# Mechanical.net
KiCad netlist of a schematic drawn in Altium Designer
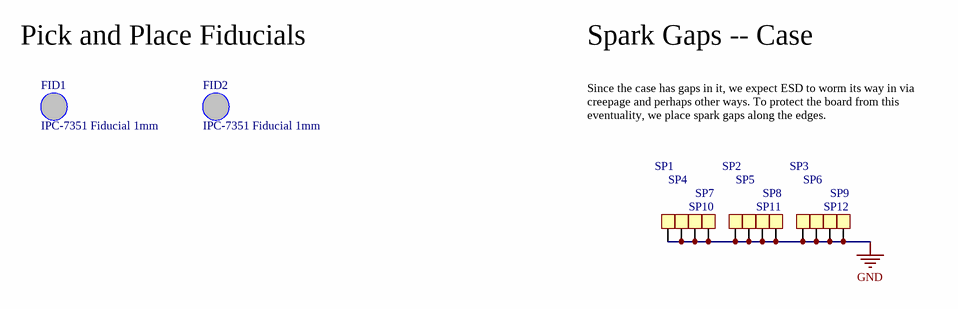
[diagram p0: Mechanical.SchDoc]

(export (version "E")
  (design (tool "Eeschema 10.0.6"))
  (components
    (comp (ref "FID1")
      (value "IPC-7351 Fiducial 1mm")
      (footprint "FIDUCIAL_1.5")
      (libsource (lib "Mechanical") (part "FIDUCIAL_1.5"))
    )
    (comp (ref "FID2")
      (value "IPC-7351 Fiducial 1mm")
      (footprint "FIDUCIAL_1.5")
      (libsource (lib "Mechanical") (part "FIDUCIAL_1.5"))
    )
    (comp (ref "SP1")
      (value "Spark Gap")
      (footprint "SparkGap")
      (description "Open square pad for spark gapping")
      (libsource (lib "PCBFeatures") (part "Spark Gap"))
    )
    (comp (ref "SP2")
      (value "Spark Gap")
      (footprint "SparkGap")
      (description "Open square pad for spark gapping")
      (libsource (lib "PCBFeatures") (part "Spark Gap"))
    )
    (comp (ref "SP3")
      (value "Spark Gap")
      (footprint "SparkGap")
      (description "Open square pad for spark gapping")
      (libsource (lib "PCBFeatures") (part "Spark Gap"))
    )
    (comp (ref "SP4")
      (value "Spark Gap")
      (footprint "SparkGap")
      (description "Open square pad for spark gapping")
      (libsource (lib "PCBFeatures") (part "Spark Gap"))
    )
    (comp (ref "SP5")
      (value "Spark Gap")
      (footprint "SparkGap")
      (description "Open square pad for spark gapping")
      (libsource (lib "PCBFeatures") (part "Spark Gap"))
    )
    (comp (ref "SP6")
      (value "Spark Gap")
      (footprint "SparkGap")
      (description "Open square pad for spark gapping")
      (libsource (lib "PCBFeatures") (part "Spark Gap"))
    )
    (comp (ref "SP7")
      (value "Spark Gap")
      (footprint "SparkGap")
      (description "Open square pad for spark gapping")
      (libsource (lib "PCBFeatures") (part "Spark Gap"))
    )
    (comp (ref "SP8")
      (value "Spark Gap")
      (footprint "SparkGap")
      (description "Open square pad for spark gapping")
      (libsource (lib "PCBFeatures") (part "Spark Gap"))
    )
    (comp (ref "SP9")
      (value "Spark Gap")
      (footprint "SparkGap")
      (description "Open square pad for spark gapping")
      (libsource (lib "PCBFeatures") (part "Spark Gap"))
    )
    (comp (ref "SP10")
      (value "Spark Gap")
      (footprint "SparkGap")
      (description "Open square pad for spark gapping")
      (libsource (lib "PCBFeatures") (part "Spark Gap"))
    )
    (comp (ref "SP11")
      (value "Spark Gap")
      (footprint "SparkGap")
      (description "Open square pad for spark gapping")
      (libsource (lib "PCBFeatures") (part "Spark Gap"))
    )
    (comp (ref "SP12")
      (value "Spark Gap")
      (footprint "SparkGap")
      (description "Open square pad for spark gapping")
      (libsource (lib "PCBFeatures") (part "Spark Gap"))
    )
  )
  (nets
    (net (code "1") (name "GND") (class "Default")
      (node (ref "SP1") (pin "1") (pinfunction "1_1") (pintype "passive"))
      (node (ref "SP10") (pin "1") (pinfunction "1_1") (pintype "passive"))
      (node (ref "SP11") (pin "1") (pinfunction "1_1") (pintype "passive"))
      (node (ref "SP12") (pin "1") (pinfunction "1_1") (pintype "passive"))
      (node (ref "SP2") (pin "1") (pinfunction "1_1") (pintype "passive"))
      (node (ref "SP3") (pin "1") (pinfunction "1_1") (pintype "passive"))
      (node (ref "SP4") (pin "1") (pinfunction "1_1") (pintype "passive"))
      (node (ref "SP5") (pin "1") (pinfunction "1_1") (pintype "passive"))
      (node (ref "SP6") (pin "1") (pinfunction "1_1") (pintype "passive"))
      (node (ref "SP7") (pin "1") (pinfunction "1_1") (pintype "passive"))
      (node (ref "SP8") (pin "1") (pinfunction "1_1") (pintype "passive"))
      (node (ref "SP9") (pin "1") (pinfunction "1_1") (pintype "passive"))
    )
    (net (code "2") (name "unconnected-(FID1-Pad1)") (class "Default")
      (node (ref "FID1") (pin "1") (pinfunction "1_1") (pintype "passive"))
    )
    (net (code "3") (name "unconnected-(FID2-Pad1)") (class "Default")
      (node (ref "FID2") (pin "1") (pinfunction "1_1") (pintype "passive"))
    )
  )
)
